# RF_liner.net
KiCad netlist of a schematic drawn in Altium Designer
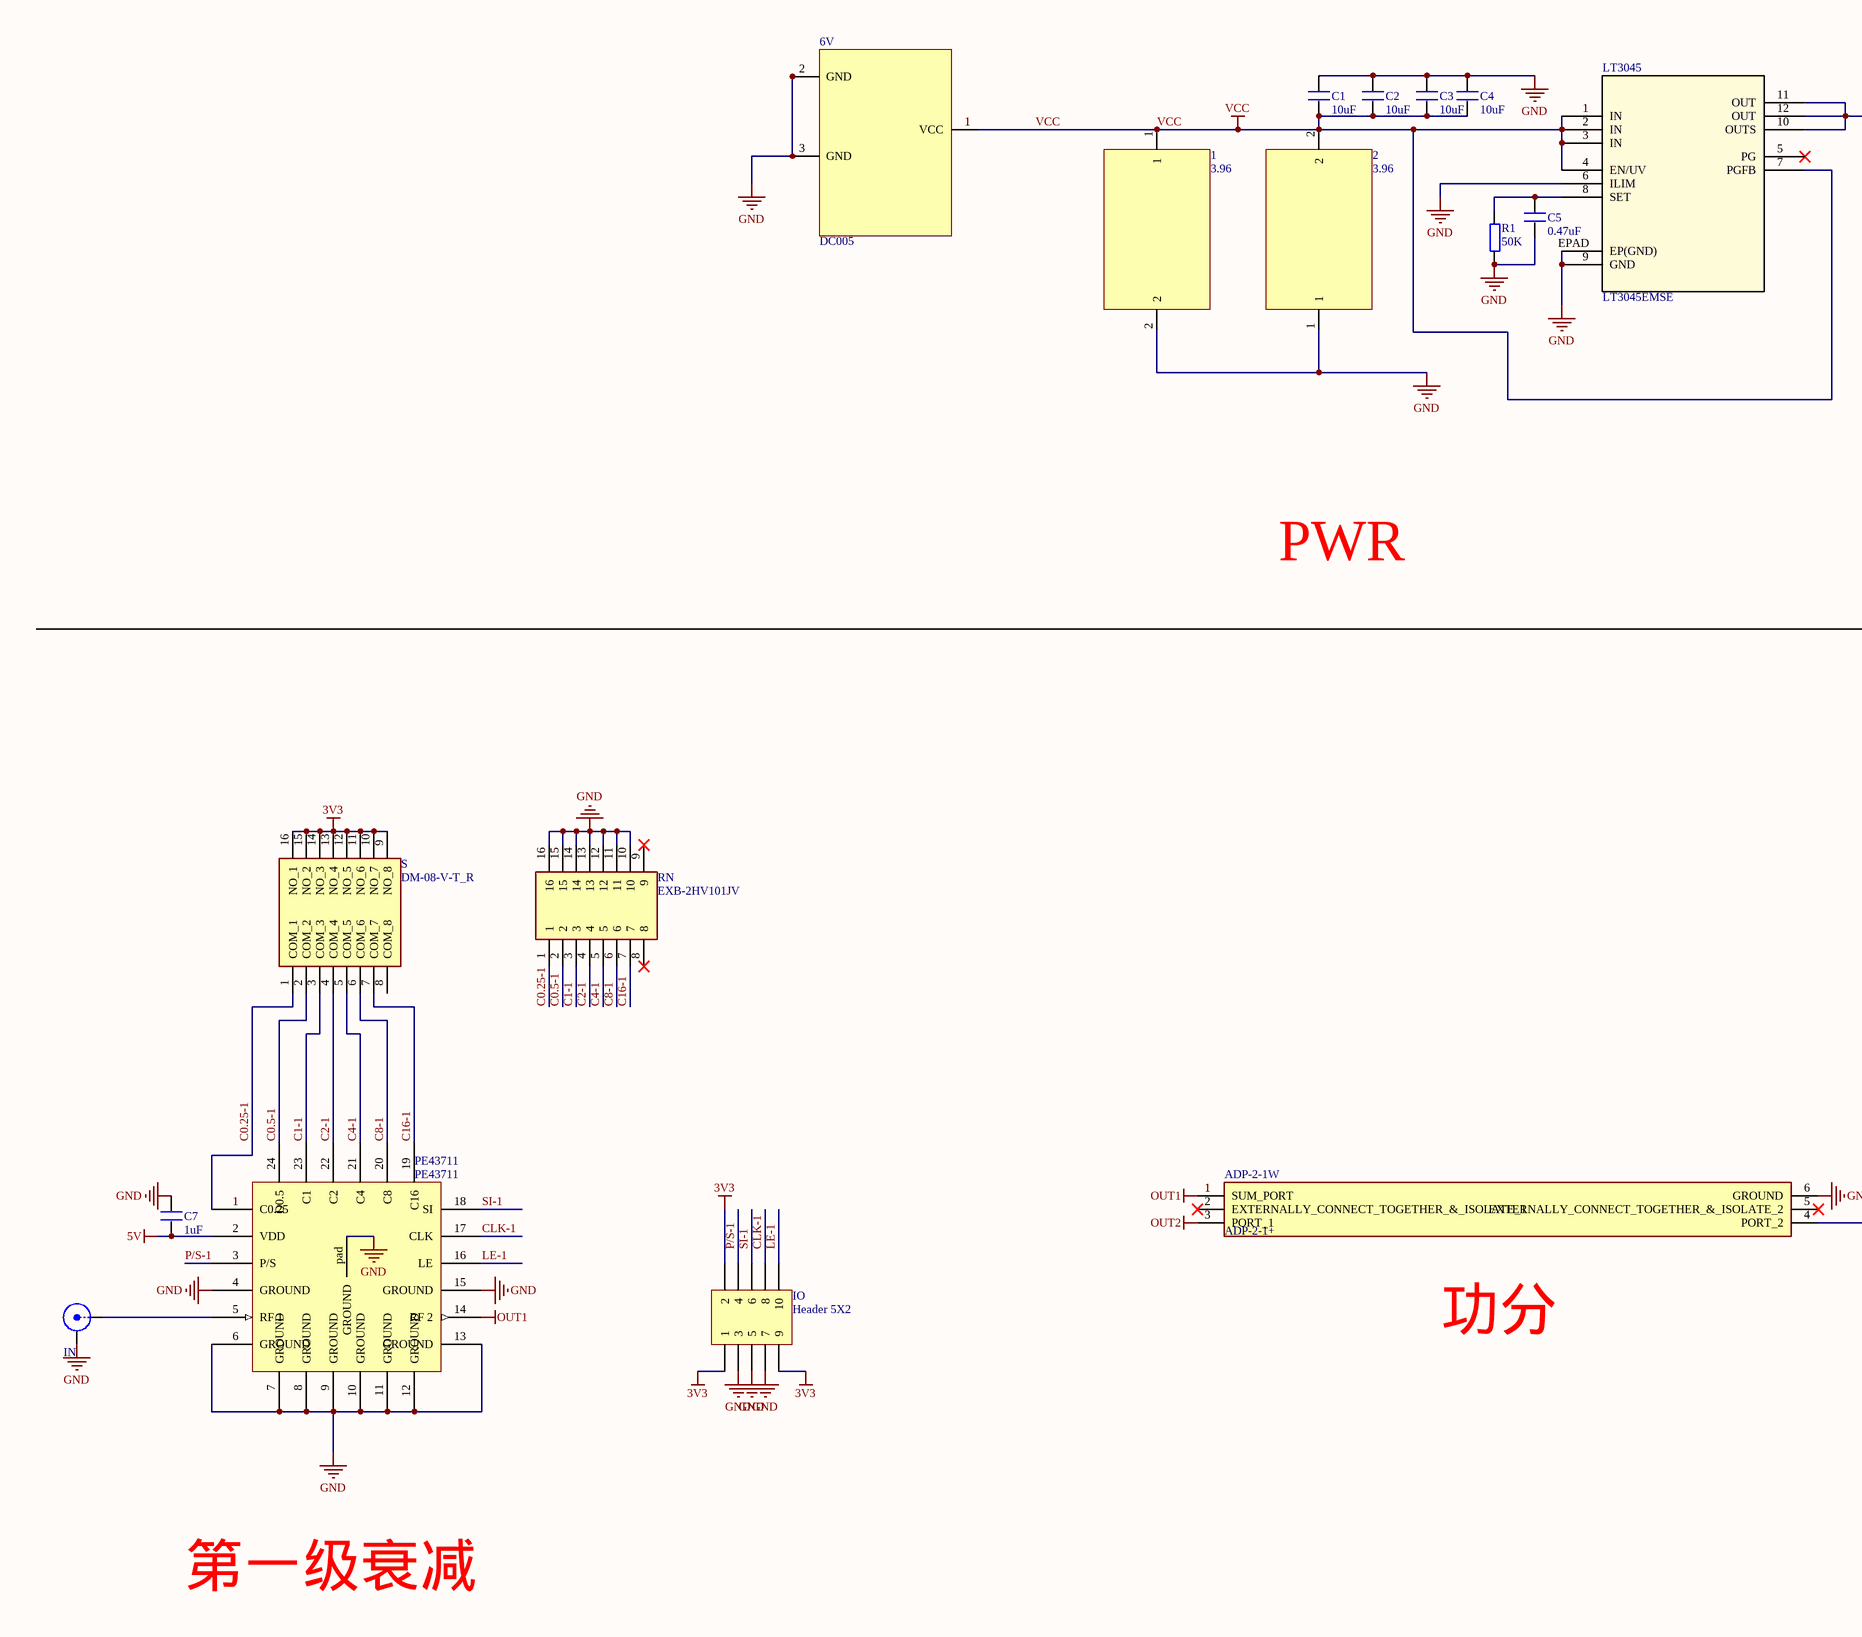
[diagram p0: RF liner.SchDoc, left]
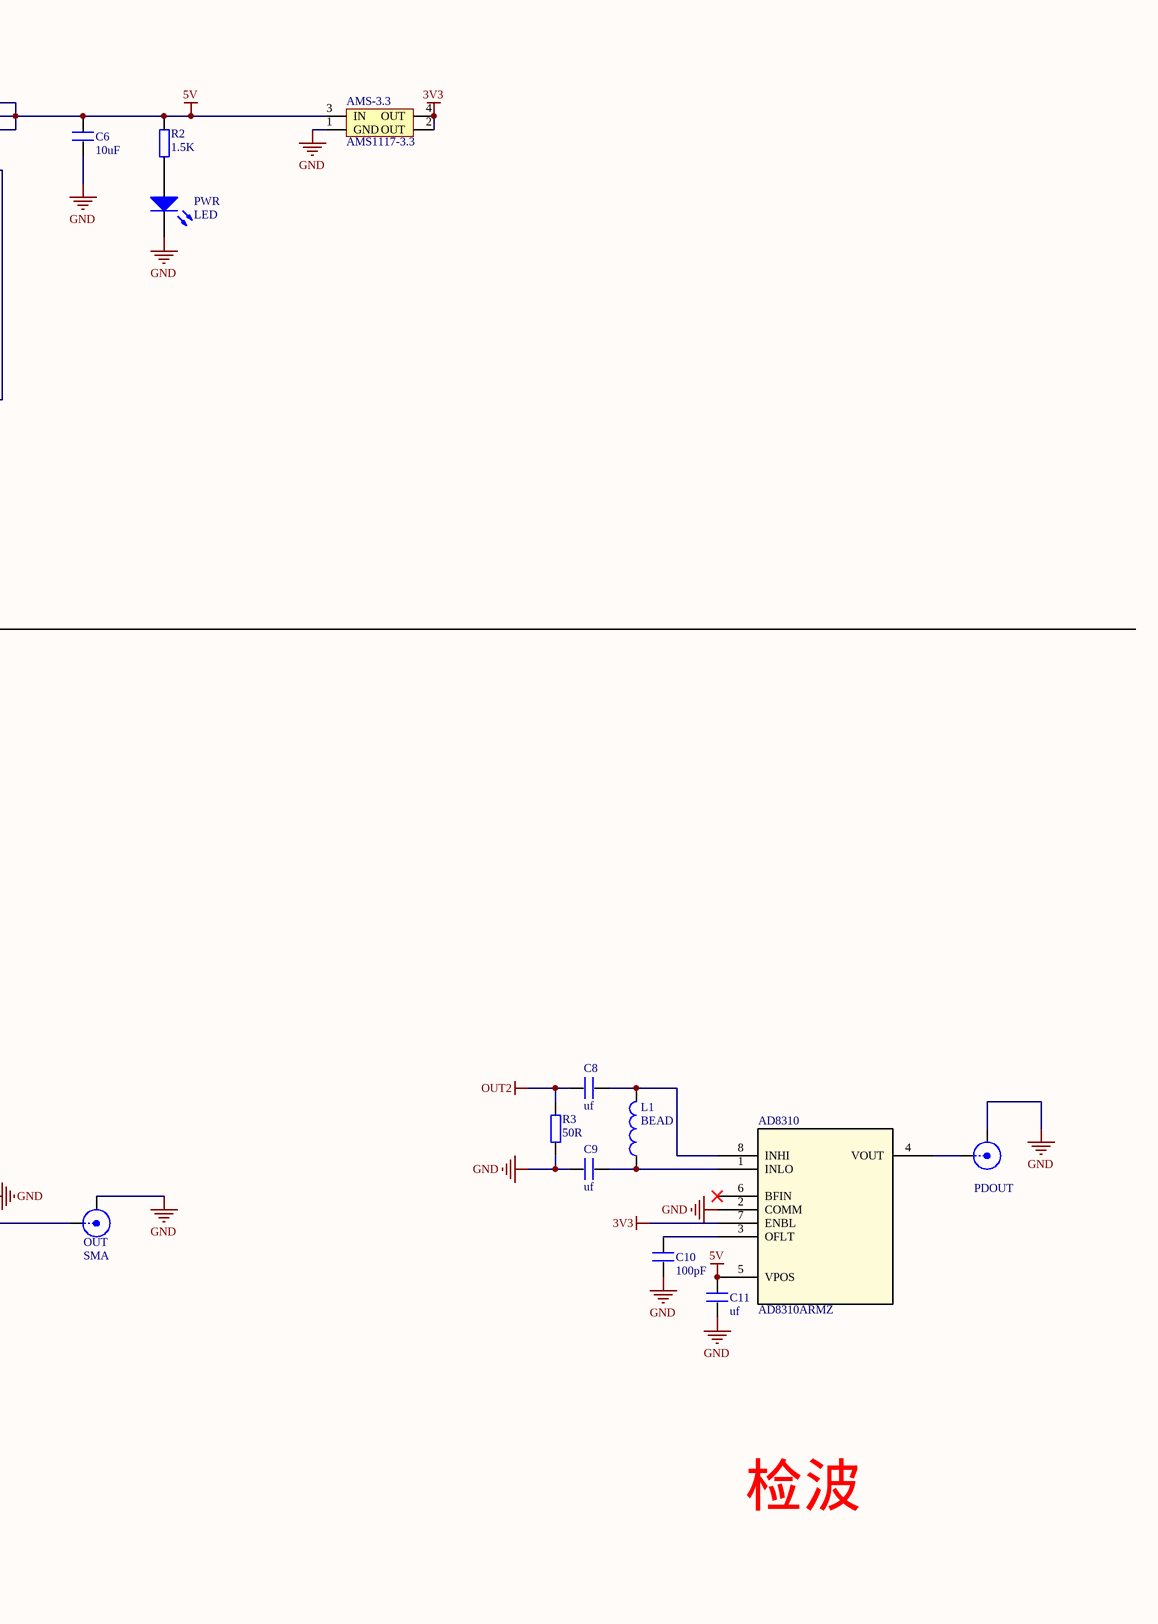
[diagram p1: RF liner.SchDoc, right]

(export (version "E")
  (design (tool "Eeschema 10.0.6"))
  (components
    (comp (ref "1") (value "3.96") (footprint "3.96") (libsource (lib "") (part "3.96_1")))
    (comp (ref "2") (value "3.96") (footprint "3.96") (libsource (lib "MYLIB") (part "3.96")))
    (comp (ref "6V") (value "DC005") (footprint "DC10B") (libsource (lib "MYLIB") (part "DC005")))
    (comp (ref "AD8310")
      (value "AD8310ARMZ")
      (footprint "RM_8_ADI")
      (description "No Description Available")
      (fields (field (name "COPYRIGHT") "Copyright (C) 2018 Accelerated Designs. All rights reserved"))
      (libsource (lib "MYLIB") (part "AD8310ARMZ"))
    )
    (comp (ref "ADP-2-1W")
      (value "ADP-2-1+")
      (footprint "MYLIB:ADP21")
      (description "Integrated Circuit")
      (fields (field (name "MOUSER PART NUMBER") "139-ADP-2-1"))
      (libsource (lib "*") (part "ADP-2-1+"))
    )
    (comp (ref "AMS-3.3")
      (value "AMS1117-3.3")
      (footprint "AMS1117")
      (libsource (lib "MYLIB") (part "AMS1117"))
    )
    (comp (ref "C1")
      (value "10uF")
      (footprint "CAP 1.5*4*8")
      (description "Capacitor")
      (libsource (lib "MYLIB") (part "C"))
    )
    (comp (ref "C2")
      (value "10uF")
      (footprint "CAP 1.5*4*8")
      (description "Capacitor")
      (libsource (lib "MYLIB") (part "C"))
    )
    (comp (ref "C3")
      (value "10uF")
      (footprint "0603C")
      (description "Capacitor")
      (libsource (lib "MYLIB") (part "C"))
    )
    (comp (ref "C4")
      (value "10uF")
      (footprint "0603C")
      (description "Capacitor")
      (libsource (lib "MYLIB") (part "C"))
    )
    (comp (ref "C5")
      (value "0.47uF")
      (footprint "0402")
      (description "Capacitor")
      (libsource (lib "MYLIB") (part "C"))
    )
    (comp (ref "C6")
      (value "10uF")
      (footprint "0402")
      (description "Capacitor")
      (libsource (lib "MYLIB") (part "C"))
    )
    (comp (ref "C7")
      (value "1uF")
      (footprint "0402")
      (description "Capacitor")
      (libsource (lib "MYLIB") (part "C"))
    )
    (comp (ref "C8")
      (value "uf")
      (footprint "0603C")
      (description "Capacitor")
      (libsource (lib "MYLIB") (part "C"))
    )
    (comp (ref "C9")
      (value "uf")
      (footprint "0603C")
      (description "Capacitor")
      (libsource (lib "MYLIB") (part "C"))
    )
    (comp (ref "C10")
      (value "100pF")
      (footprint "0603C")
      (description "Capacitor")
      (libsource (lib "MYLIB") (part "C"))
    )
    (comp (ref "C11")
      (value "uf")
      (footprint "0603C")
      (description "Capacitor")
      (libsource (lib "MYLIB") (part "C"))
    )
    (comp (ref "IN")
      (value "SMA")
      (footprint "SMA")
      (description "SMA Connector")
      (libsource (lib "MYLIB") (part "SMA"))
    )
    (comp (ref "IO")
      (value "Header 5X2")
      (footprint "HDR2X5")
      (description "Header, 5-Pin, Dual row")
      (fields (field (name "PUBLISHER") "Altium Limited"))
      (libsource (lib "Miscellaneous Connectors") (part "Header 5X2"))
    )
    (comp (ref "L1")
      (value "BEAD")
      (footprint "0603L")
      (description "Inductor")
      (fields (field (name "PUBLISHER") "Altium Limited"))
      (libsource (lib "MYLIB") (part "Inductor"))
    )
    (comp (ref "LT3045")
      (value "LT3045EMSE")
      (footprint "MSOP12-MSE-RevG_ADI")
      (description "No Description Available")
      (fields (field (name "COPYRIGHT") "Copyright (C) 2018 Accelerated Designs. All rights reserved"))
      (libsource (lib "MYLIB") (part "LT3045EMSE"))
    )
    (comp (ref "OUT")
      (value "SMA")
      (footprint "SMA")
      (description "SMA Connector")
      (libsource (lib "MYLIB") (part "SMA"))
    )
    (comp (ref "PDOUT")
      (value "SMA")
      (footprint "SMA")
      (description "SMA Connector")
      (libsource (lib "MYLIB") (part "SMA"))
    )
    (comp (ref "PE43711") (value "PE43711") (footprint "PE43711") (libsource (lib "MYLIB") (part "PE43711")))
    (comp (ref "PWR")
      (value "LED")
      (footprint "SMDLED")
      (description "Typical RED, GREEN, YELLOW, AMBER GaAs LED")
      (fields (field (name "PUBLISHER") "Altium Limited"))
      (libsource (lib "MYLIB") (part "LED"))
    )
    (comp (ref "R1")
      (value "50K")
      (footprint "0402")
      (description "Resistor")
      (libsource (lib "MYLIB") (part "Resistor"))
    )
    (comp (ref "R2")
      (value "1.5K")
      (footprint "0603R")
      (description "Resistor")
      (libsource (lib "MYLIB") (part "Resistor"))
    )
    (comp (ref "R3")
      (value "50R")
      (footprint "0603R")
      (description "Resistor")
      (libsource (lib "MYLIB") (part "Resistor"))
    )
    (comp (ref "RN")
      (value "EXB-2HV101JV")
      (footprint "MYLIB:EXB2HV101JV")
      (description "Resistor Network")
      (fields (field (name "MOUSER PART NUMBER") "667-EXB-2HV101JV"))
      (libsource (lib "MYLIB") (part "EXB-2HV101JV"))
    )
    (comp (ref "S")
      (value "DM-08-V-T_R")
      (footprint "MYLIB:DM08VTR")
      (description "Switch")
      (fields (field (name "MANUFACTURER_PART_NUMBER") "DM-08-V-T/R"))
      (libsource (lib "*") (part "DM-08-V-T_R"))
    )
  )
  (nets
    (net (code "1") (name "/C0.5-1") (class "Default")
      (node (ref "PE43711") (pin "24") (pinfunction "D0.5_24") (pintype "passive"))
      (node (ref "RN") (pin "2") (pinfunction "2_2") (pintype "passive"))
      (node (ref "S") (pin "2") (pinfunction "COM_2_2") (pintype "passive"))
    )
    (net (code "2") (name "/C0.25-1") (class "Default")
      (node (ref "PE43711") (pin "1") (pinfunction "C0.25_1") (pintype "open_collector"))
      (node (ref "RN") (pin "1") (pinfunction "1_1") (pintype "passive"))
      (node (ref "S") (pin "1") (pinfunction "COM_1_1") (pintype "passive"))
    )
    (net (code "3") (name "/C1-1") (class "Default")
      (node (ref "PE43711") (pin "23") (pinfunction "C1_23") (pintype "passive"))
      (node (ref "RN") (pin "3") (pinfunction "3_3") (pintype "passive"))
      (node (ref "S") (pin "3") (pinfunction "COM_3_3") (pintype "passive"))
    )
    (net (code "4") (name "/C2-1") (class "Default")
      (node (ref "PE43711") (pin "22") (pinfunction "C2_22") (pintype "passive"))
      (node (ref "RN") (pin "4") (pinfunction "4_4") (pintype "passive"))
      (node (ref "S") (pin "4") (pinfunction "COM_4_4") (pintype "passive"))
    )
    (net (code "5") (name "/C4-1") (class "Default")
      (node (ref "PE43711") (pin "21") (pinfunction "C4_21") (pintype "passive"))
      (node (ref "RN") (pin "5") (pinfunction "5_5") (pintype "passive"))
      (node (ref "S") (pin "5") (pinfunction "COM_5_5") (pintype "passive"))
    )
    (net (code "6") (name "/C8-1") (class "Default")
      (node (ref "PE43711") (pin "20") (pinfunction "C8_20") (pintype "passive"))
      (node (ref "RN") (pin "6") (pinfunction "6_6") (pintype "passive"))
      (node (ref "S") (pin "6") (pinfunction "COM_6_6") (pintype "passive"))
    )
    (net (code "7") (name "/C16-1") (class "Default")
      (node (ref "PE43711") (pin "19") (pinfunction "C16_19") (pintype "open_collector"))
      (node (ref "RN") (pin "7") (pinfunction "7_7") (pintype "passive"))
      (node (ref "S") (pin "7") (pinfunction "COM_7_7") (pintype "passive"))
    )
    (net (code "8") (name "/CLK-1") (class "Default")
      (node (ref "IO") (pin "8") (pinfunction "8_8") (pintype "passive"))
      (node (ref "PE43711") (pin "17") (pinfunction "CLK_17") (pintype "passive"))
    )
    (net (code "9") (name "/LE-1") (class "Default")
      (node (ref "IO") (pin "10") (pinfunction "10_10") (pintype "passive"))
      (node (ref "PE43711") (pin "16") (pinfunction "LE_16") (pintype "passive"))
    )
    (net (code "10") (name "/P{slash}S-1") (class "Default")
      (node (ref "IO") (pin "4") (pinfunction "4_4") (pintype "passive"))
      (node (ref "PE43711") (pin "3") (pinfunction "P/S_3") (pintype "passive"))
    )
    (net (code "11") (name "/SI-1") (class "Default")
      (node (ref "IO") (pin "6") (pinfunction "6_6") (pintype "passive"))
      (node (ref "PE43711") (pin "18") (pinfunction "SI_18") (pintype "passive"))
    )
    (net (code "12") (name "3V3") (class "Default")
      (node (ref "AD8310") (pin "7") (pinfunction "ENBL_7") (pintype "passive"))
      (node (ref "AMS-3.3") (pin "2") (pinfunction "OUT_2") (pintype "passive"))
      (node (ref "AMS-3.3") (pin "4") (pinfunction "OUT_4") (pintype "passive"))
      (node (ref "IO") (pin "1") (pinfunction "1_1") (pintype "passive"))
      (node (ref "IO") (pin "2") (pinfunction "2_2") (pintype "passive"))
      (node (ref "IO") (pin "9") (pinfunction "9_9") (pintype "passive"))
      (node (ref "S") (pin "10") (pinfunction "NO_7_10") (pintype "passive"))
      (node (ref "S") (pin "11") (pinfunction "NO_6_11") (pintype "passive"))
      (node (ref "S") (pin "12") (pinfunction "NO_5_12") (pintype "passive"))
      (node (ref "S") (pin "13") (pinfunction "NO_4_13") (pintype "passive"))
      (node (ref "S") (pin "14") (pinfunction "NO_3_14") (pintype "passive"))
      (node (ref "S") (pin "15") (pinfunction "NO_2_15") (pintype "passive"))
      (node (ref "S") (pin "16") (pinfunction "NO_1_16") (pintype "passive"))
      (node (ref "S") (pin "9") (pinfunction "NO_8_9") (pintype "passive"))
    )
    (net (code "13") (name "5V") (class "Default")
      (node (ref "AD8310") (pin "5") (pinfunction "VPOS_5") (pintype "power_in"))
      (node (ref "AMS-3.3") (pin "3") (pinfunction "IN_3") (pintype "passive"))
      (node (ref "C11") (pin "2") (pintype "passive"))
      (node (ref "C6") (pin "2") (pintype "passive"))
      (node (ref "C7") (pin "1") (pintype "passive"))
      (node (ref "LT3045") (pin "10") (pinfunction "OUTS_10") (pintype "passive"))
      (node (ref "LT3045") (pin "11") (pinfunction "OUT_11") (pintype "passive"))
      (node (ref "LT3045") (pin "12") (pinfunction "OUT_12") (pintype "passive"))
      (node (ref "PE43711") (pin "2") (pinfunction "VDD_2") (pintype "power_in"))
      (node (ref "R2") (pin "2") (pintype "passive"))
    )
    (net (code "14") (name "GND") (class "Default")
      (node (ref "1") (pin "2") (pinfunction "2_2") (pintype "passive"))
      (node (ref "2") (pin "1") (pinfunction "1_1") (pintype "passive"))
      (node (ref "6V") (pin "2") (pinfunction "GND_2") (pintype "passive"))
      (node (ref "6V") (pin "3") (pinfunction "GND_3") (pintype "passive"))
      (node (ref "AD8310") (pin "2") (pinfunction "COMM_2") (pintype "passive"))
      (node (ref "ADP-2-1W") (pin "6") (pinfunction "GROUND_6") (pintype "passive"))
      (node (ref "AMS-3.3") (pin "1") (pinfunction "GND_1") (pintype "passive"))
      (node (ref "C1") (pin "2") (pintype "passive"))
      (node (ref "C10") (pin "1") (pintype "passive"))
      (node (ref "C11") (pin "1") (pintype "passive"))
      (node (ref "C2") (pin "2") (pintype "passive"))
      (node (ref "C3") (pin "2") (pintype "passive"))
      (node (ref "C4") (pin "2") (pintype "passive"))
      (node (ref "C5") (pin "2") (pintype "passive"))
      (node (ref "C6") (pin "1") (pintype "passive"))
      (node (ref "C7") (pin "2") (pintype "passive"))
      (node (ref "C9") (pin "1") (pintype "passive"))
      (node (ref "IN") (pin "2") (pinfunction "Y_2") (pintype "passive"))
      (node (ref "IO") (pin "3") (pinfunction "3_3") (pintype "passive"))
      (node (ref "IO") (pin "5") (pinfunction "5_5") (pintype "passive"))
      (node (ref "IO") (pin "7") (pinfunction "7_7") (pintype "passive"))
      (node (ref "LT3045") (pin "6") (pinfunction "ILIM_6") (pintype "passive"))
      (node (ref "LT3045") (pin "9") (pinfunction "GND_9") (pintype "passive"))
      (node (ref "LT3045") (pin "EPAD") (pinfunction "EP(GND)_EPAD") (pintype "passive"))
      (node (ref "OUT") (pin "2") (pinfunction "Y_2") (pintype "passive"))
      (node (ref "PDOUT") (pin "2") (pinfunction "Y_2") (pintype "passive"))
      (node (ref "PE43711") (pin "10") (pinfunction "GROUND_10") (pintype "passive"))
      (node (ref "PE43711") (pin "11") (pinfunction "GROUND_11") (pintype "passive"))
      (node (ref "PE43711") (pin "12") (pinfunction "GROUND_12") (pintype "passive"))
      (node (ref "PE43711") (pin "13") (pinfunction "GROUND_13") (pintype "passive"))
      (node (ref "PE43711") (pin "15") (pinfunction "GROUND_15") (pintype "passive"))
      (node (ref "PE43711") (pin "4") (pinfunction "GROUND_4") (pintype "passive"))
      (node (ref "PE43711") (pin "6") (pinfunction "GROUND_6") (pintype "passive"))
      (node (ref "PE43711") (pin "7") (pinfunction "GROUND_7") (pintype "passive"))
      (node (ref "PE43711") (pin "8") (pinfunction "GROUND_8") (pintype "passive"))
      (node (ref "PE43711") (pin "9") (pinfunction "GROUND_9") (pintype "passive"))
      (node (ref "PE43711") (pin "pad") (pinfunction "GROUND_pad") (pintype "passive"))
      (node (ref "PWR") (pin "2") (pinfunction "K_2") (pintype "passive"))
      (node (ref "R1") (pin "1") (pintype "passive"))
      (node (ref "R3") (pin "1") (pintype "passive"))
      (node (ref "RN") (pin "10") (pinfunction "10_10") (pintype "passive"))
      (node (ref "RN") (pin "11") (pinfunction "11_11") (pintype "passive"))
      (node (ref "RN") (pin "12") (pinfunction "12_12") (pintype "passive"))
      (node (ref "RN") (pin "13") (pinfunction "13_13") (pintype "passive"))
      (node (ref "RN") (pin "14") (pinfunction "14_14") (pintype "passive"))
      (node (ref "RN") (pin "15") (pinfunction "15_15") (pintype "passive"))
      (node (ref "RN") (pin "16") (pinfunction "16_16") (pintype "passive"))
    )
    (net (code "15") (name "Net-(AD8310-INHI)") (class "Default")
      (node (ref "AD8310") (pin "8") (pinfunction "INHI_8") (pintype "passive"))
      (node (ref "C8") (pin "2") (pintype "passive"))
      (node (ref "L1") (pin "2") (pinfunction "2_2") (pintype "passive"))
    )
    (net (code "16") (name "Net-(AD8310-INLO)") (class "Default")
      (node (ref "AD8310") (pin "1") (pinfunction "INLO_1") (pintype "passive"))
      (node (ref "C9") (pin "2") (pintype "passive"))
      (node (ref "L1") (pin "1") (pinfunction "1_1") (pintype "passive"))
    )
    (net (code "17") (name "Net-(AD8310-OFLT)") (class "Default")
      (node (ref "AD8310") (pin "3") (pinfunction "OFLT_3") (pintype "passive"))
      (node (ref "C10") (pin "2") (pintype "passive"))
    )
    (net (code "18") (name "Net-(AD8310-VOUT)") (class "Default")
      (node (ref "AD8310") (pin "4") (pinfunction "VOUT_4") (pintype "passive"))
      (node (ref "PDOUT") (pin "1") (pinfunction "X_1") (pintype "passive"))
    )
    (net (code "19") (name "Net-(ADP-2-1W-PORT_2)") (class "Default")
      (node (ref "ADP-2-1W") (pin "4") (pinfunction "PORT_2_4") (pintype "passive"))
      (node (ref "OUT") (pin "1") (pinfunction "X_1") (pintype "passive"))
    )
    (net (code "20") (name "Net-(IN-X)") (class "Default")
      (node (ref "IN") (pin "1") (pinfunction "X_1") (pintype "passive"))
      (node (ref "PE43711") (pin "5") (pinfunction "RF_1_5") (pintype "input"))
    )
    (net (code "21") (name "Net-(LT3045-SET)") (class "Default")
      (node (ref "C5") (pin "1") (pintype "passive"))
      (node (ref "LT3045") (pin "8") (pinfunction "SET_8") (pintype "passive"))
      (node (ref "R1") (pin "2") (pintype "passive"))
    )
    (net (code "22") (name "Net-(PWR-A)") (class "Default")
      (node (ref "PWR") (pin "1") (pinfunction "A_1") (pintype "passive"))
      (node (ref "R2") (pin "1") (pintype "passive"))
    )
    (net (code "23") (name "OUT1") (class "Default")
      (node (ref "ADP-2-1W") (pin "1") (pinfunction "SUM_PORT_1") (pintype "passive"))
      (node (ref "PE43711") (pin "14") (pinfunction "RF_2_14") (pintype "output"))
    )
    (net (code "24") (name "OUT2") (class "Default")
      (node (ref "ADP-2-1W") (pin "3") (pinfunction "PORT_1_3") (pintype "passive"))
      (node (ref "C8") (pin "1") (pintype "passive"))
      (node (ref "R3") (pin "2") (pintype "passive"))
    )
    (net (code "25") (name "VCC") (class "Default")
      (node (ref "1") (pin "1") (pinfunction "1_1") (pintype "passive"))
      (node (ref "2") (pin "2") (pinfunction "2_2") (pintype "passive"))
      (node (ref "6V") (pin "1") (pinfunction "VCC_1") (pintype "passive"))
      (node (ref "C1") (pin "1") (pintype "passive"))
      (node (ref "C2") (pin "1") (pintype "passive"))
      (node (ref "C3") (pin "1") (pintype "passive"))
      (node (ref "C4") (pin "1") (pintype "passive"))
      (node (ref "LT3045") (pin "1") (pinfunction "IN_1") (pintype "passive"))
      (node (ref "LT3045") (pin "2") (pinfunction "IN_2") (pintype "passive"))
      (node (ref "LT3045") (pin "3") (pinfunction "IN_3") (pintype "passive"))
      (node (ref "LT3045") (pin "4") (pinfunction "EN/UV_4") (pintype "passive"))
      (node (ref "LT3045") (pin "7") (pinfunction "PGFB_7") (pintype "passive"))
    )
    (net (code "26") (name "unconnected-(AD8310-BFIN-Pad6)") (class "Default")
      (node (ref "AD8310") (pin "6") (pinfunction "BFIN_6") (pintype "passive+no_connect"))
    )
    (net (code "27") (name "unconnected-(ADP-2-1W-EXTERNALLY_CONNECT_TOGETHER_&_ISOLATE_1-Pad2)") (class "Default")
      (node (ref "ADP-2-1W") (pin "2") (pinfunction "EXTERNALLY_CONNECT_TOGETHER_&_ISOLATE_1_2") (pintype "passive+no_connect"))
    )
    (net (code "28") (name "unconnected-(ADP-2-1W-EXTERNALLY_CONNECT_TOGETHER_&_ISOLATE_2-Pad5)") (class "Default")
      (node (ref "ADP-2-1W") (pin "5") (pinfunction "EXTERNALLY_CONNECT_TOGETHER_&_ISOLATE_2_5") (pintype "passive+no_connect"))
    )
    (net (code "29") (name "unconnected-(LT3045-PG-Pad5)") (class "Default")
      (node (ref "LT3045") (pin "5") (pinfunction "PG_5") (pintype "passive+no_connect"))
    )
    (net (code "30") (name "unconnected-(RN-Pad8)") (class "Default")
      (node (ref "RN") (pin "8") (pinfunction "8_8") (pintype "passive+no_connect"))
    )
    (net (code "31") (name "unconnected-(RN-Pad9)") (class "Default")
      (node (ref "RN") (pin "9") (pinfunction "9_9") (pintype "passive+no_connect"))
    )
    (net (code "32") (name "unconnected-(S-COM_8-Pad8)") (class "Default")
      (node (ref "S") (pin "8") (pinfunction "COM_8_8") (pintype "passive"))
    )
  )
)
